# Buttons.net
KiCad netlist of a schematic drawn in Altium Designer
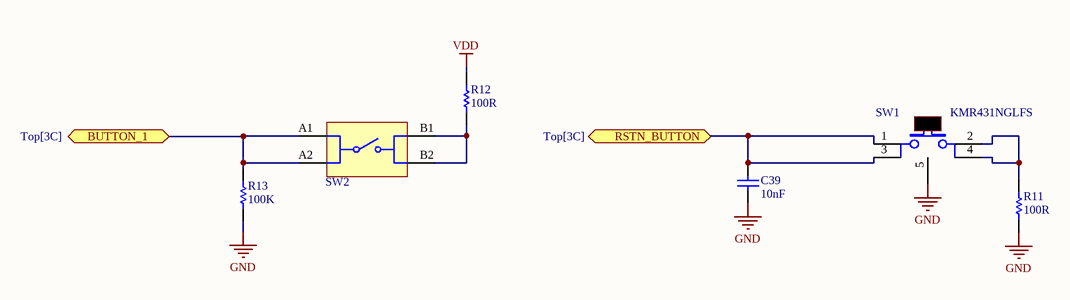
[diagram p0: Buttons.SchDoc]

(export (version "E")
  (design (tool "Eeschema 10.0.6"))
  (components
    (comp (ref "C39")
      (value "10nF")
      (footprint "C0402")
      (description "Capacitor, MLCC, 10nF, 16V, X7R, +/-10%, 0402, T=0.5mm")
      (fields (field (name "INTERNAL_PART_NUMBER") "MCD-00011") (field (name "MANUFACTURER") "YAGEO"))
      (libsource (lib "MCD_PARTS_database") (part "Capacitor"))
    )
    (comp (ref "R11")
      (value "100R")
      (footprint "R0402")
      (description "Resistor, 100R, 0402, +/-0.1%, 1/16W, +/-25ppm/°C")
      (fields (field (name "INTERNAL_PART_NUMBER") "MCD-02655") (field (name "MANUFACTURER") "YAGEO"))
      (libsource (lib "MCD_PARTS_database") (part "Resistor"))
    )
    (comp (ref "R12")
      (value "100R")
      (footprint "R0402")
      (description "Resistor, 100R, 0402, +/-0.1%, 1/16W, +/-25ppm/°C")
      (fields (field (name "INTERNAL_PART_NUMBER") "MCD-02655") (field (name "MANUFACTURER") "YAGEO"))
      (libsource (lib "MCD_PARTS_database") (part "Resistor"))
    )
    (comp (ref "R13")
      (value "100K")
      (footprint "R0402")
      (description "Resistor, 100K, 0402, +/-1%, 1/16W")
      (fields (field (name "INTERNAL_PART_NUMBER") "MCD-00059") (field (name "MANUFACTURER") "YAGEO"))
      (libsource (lib "MCD_PARTS_database") (part "Resistor"))
    )
    (comp (ref "SW1")
      (value "KMR431NGLFS")
      (footprint "SWI_C&K_Y78B23110FP__ITT_KMR231GLFS")
      (description "Switch tactile, SPST-NO, 32V, 50mA, 2.8x4.6mm")
      (fields (field (name "INTERNAL_PART_NUMBER") "MCD-00715") (field (name "MANUFACTURER") "C&K"))
      (libsource (lib "MCD_PARTS_database") (part "SW-PUSH-CMS_BLACK_PIN1-3_2-4"))
    )
    (comp (ref "SW2")
      (value "434351045816")
      (footprint "434351045816")
      (description "WS-TASU SMT Tact Switch 4.7x3.5mm side push, SPST-NO, 12VDC, 50mA, 160g")
      (fields (field (name "MANUFACTURER") "Wurth Elektronik"))
      (libsource (lib "STEVAL-ESLBLECB") (part "434351045816"))
    )
  )
  (nets
    (net (code "1") (name "/BUTTON_1") (class "Default")
      (node (ref "R13") (pin "2") (pinfunction "2_2") (pintype "passive"))
      (node (ref "SW2") (pin "A1") (pinfunction "A1_A1") (pintype "passive"))
      (node (ref "SW2") (pin "A2") (pinfunction "A2_A2") (pintype "passive"))
    )
    (net (code "2") (name "/RSTN_BUTTON") (class "Default")
      (node (ref "C39") (pin "2") (pinfunction "2_2") (pintype "passive"))
      (node (ref "SW1") (pin "1") (pinfunction "1_1") (pintype "passive"))
      (node (ref "SW1") (pin "3") (pinfunction "3_3") (pintype "passive"))
    )
    (net (code "3") (name "GND") (class "Default")
      (node (ref "C39") (pin "1") (pinfunction "1_1") (pintype "passive"))
      (node (ref "R11") (pin "1") (pinfunction "1_1") (pintype "passive"))
      (node (ref "R13") (pin "1") (pinfunction "1_1") (pintype "passive"))
      (node (ref "SW1") (pin "5") (pinfunction "GND_5") (pintype "passive"))
    )
    (net (code "4") (name "Net-(R11-Pad2)") (class "Default")
      (node (ref "R11") (pin "2") (pinfunction "2_2") (pintype "passive"))
      (node (ref "SW1") (pin "2") (pinfunction "2_2") (pintype "passive"))
      (node (ref "SW1") (pin "4") (pinfunction "4_4") (pintype "passive"))
    )
    (net (code "5") (name "Net-(R12-Pad1)") (class "Default")
      (node (ref "R12") (pin "1") (pinfunction "1_1") (pintype "passive"))
      (node (ref "SW2") (pin "B1") (pinfunction "B1_B1") (pintype "passive"))
      (node (ref "SW2") (pin "B2") (pinfunction "B2_B2") (pintype "passive"))
    )
    (net (code "6") (name "VDD") (class "Default")
      (node (ref "R12") (pin "2") (pinfunction "2_2") (pintype "passive"))
    )
  )
)
